# led-shift-r1.net
KiCad netlist of a schematic drawn in EAGLE
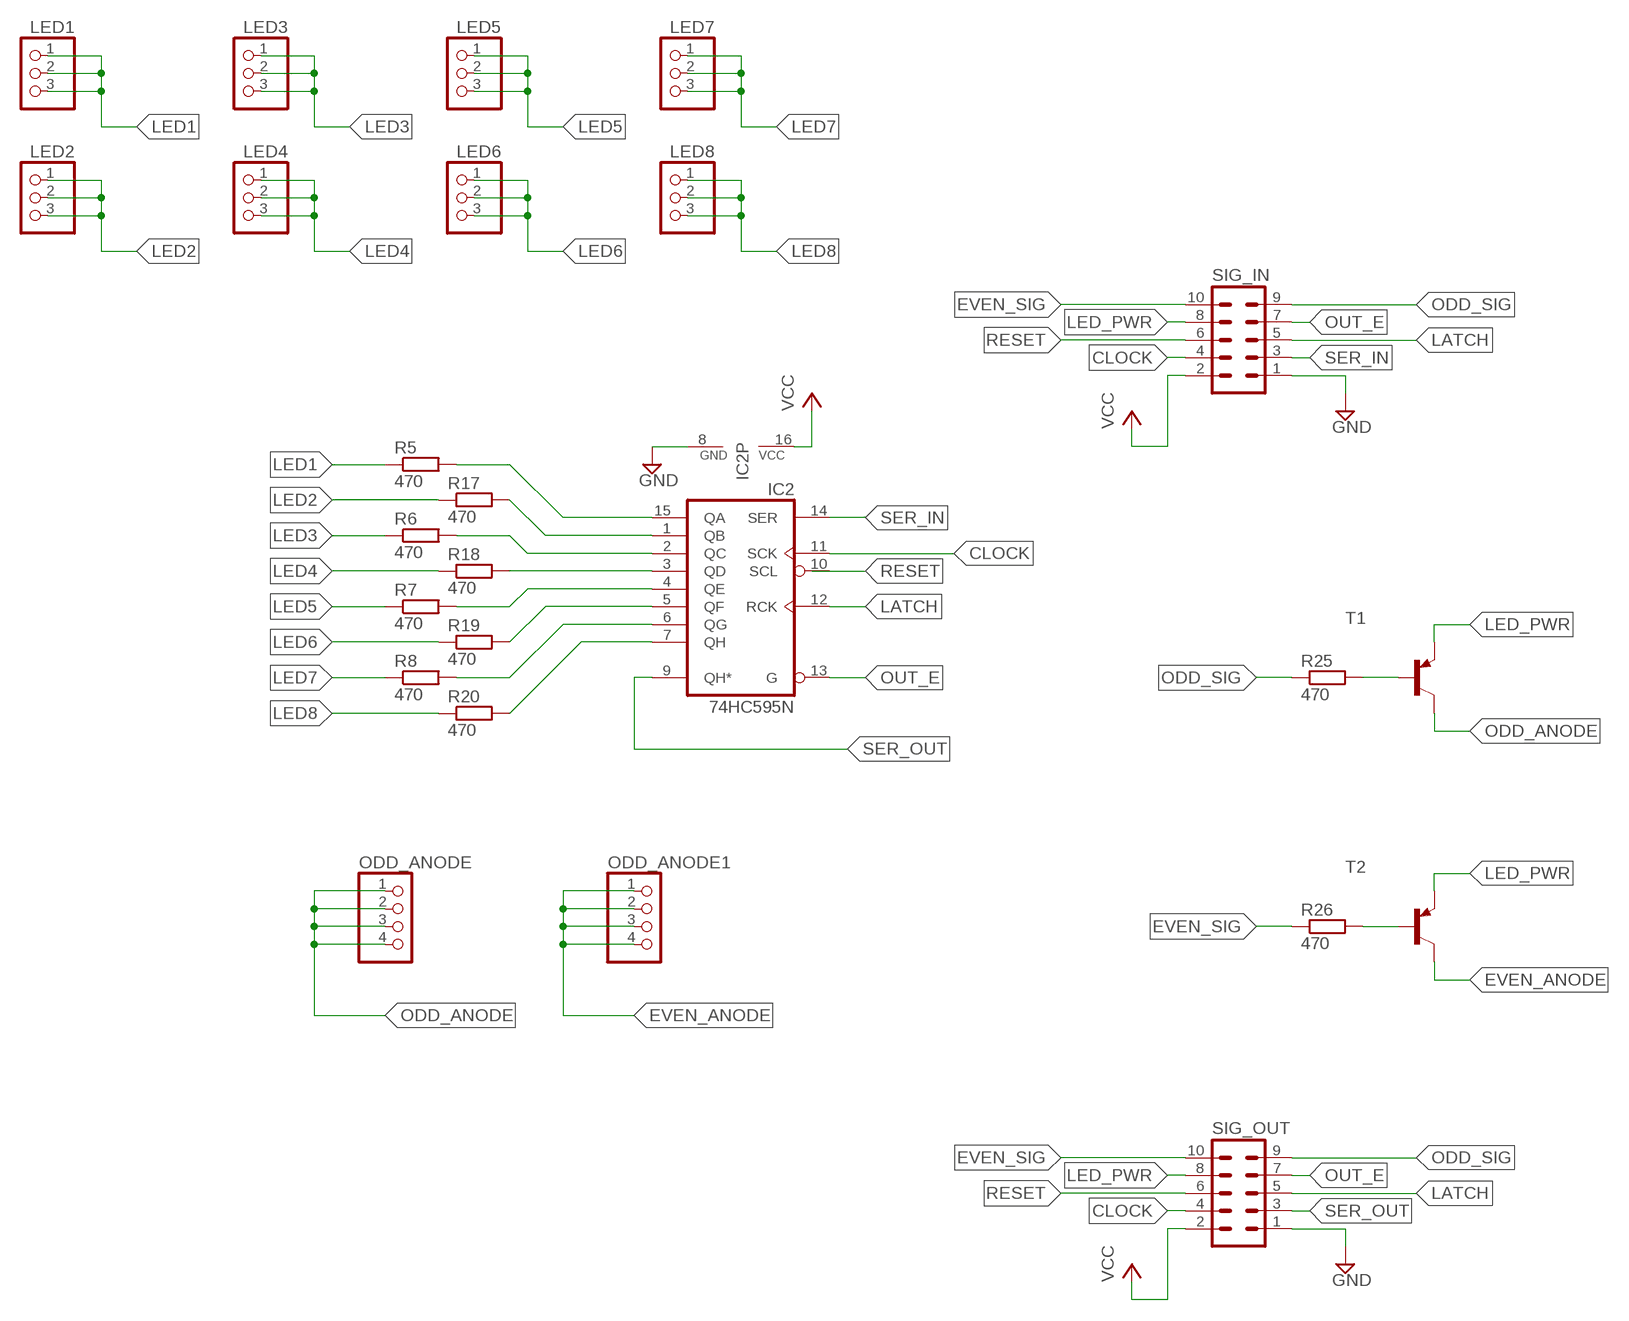
[diagram p0: schematic, sheet 1]

(export (version "E")
  (design (tool "Eeschema 10.0.6"))
  (components
    (comp (ref "IC2")
      (value "74HC595N")
      (footprint "eagle-import:DIL16")
      (libsource (lib "eagle-import") (part "74595NHC"))
    )
    (comp (ref "LED1")
      (value "PINHD-1X3")
      (footprint "eagle-import:1X03")
      (libsource (lib "eagle-import") (part "PINHD-1X3"))
    )
    (comp (ref "LED2")
      (value "PINHD-1X3")
      (footprint "eagle-import:1X03")
      (libsource (lib "eagle-import") (part "PINHD-1X3"))
    )
    (comp (ref "LED3")
      (value "PINHD-1X3")
      (footprint "eagle-import:1X03")
      (libsource (lib "eagle-import") (part "PINHD-1X3"))
    )
    (comp (ref "LED4")
      (value "PINHD-1X3")
      (footprint "eagle-import:1X03")
      (libsource (lib "eagle-import") (part "PINHD-1X3"))
    )
    (comp (ref "LED5")
      (value "PINHD-1X3")
      (footprint "eagle-import:1X03")
      (libsource (lib "eagle-import") (part "PINHD-1X3"))
    )
    (comp (ref "LED6")
      (value "PINHD-1X3")
      (footprint "eagle-import:1X03")
      (libsource (lib "eagle-import") (part "PINHD-1X3"))
    )
    (comp (ref "LED7")
      (value "PINHD-1X3")
      (footprint "eagle-import:1X03")
      (libsource (lib "eagle-import") (part "PINHD-1X3"))
    )
    (comp (ref "LED8")
      (value "PINHD-1X3")
      (footprint "eagle-import:1X03")
      (libsource (lib "eagle-import") (part "PINHD-1X3"))
    )
    (comp (ref "ODD_ANODE")
      (value "PINHD-1X4")
      (footprint "eagle-import:1X04")
      (libsource (lib "eagle-import") (part "PINHD-1X4"))
    )
    (comp (ref "ODD_ANODE1")
      (value "PINHD-1X4")
      (footprint "eagle-import:1X04")
      (libsource (lib "eagle-import") (part "PINHD-1X4"))
    )
    (comp (ref "R5")
      (value "470")
      (footprint "eagle-import:R0805")
      (libsource (lib "eagle-import") (part "R-EU_R0805"))
    )
    (comp (ref "R6")
      (value "470")
      (footprint "eagle-import:R0805")
      (libsource (lib "eagle-import") (part "R-EU_R0805"))
    )
    (comp (ref "R7")
      (value "470")
      (footprint "eagle-import:R0805")
      (libsource (lib "eagle-import") (part "R-EU_R0805"))
    )
    (comp (ref "R8")
      (value "470")
      (footprint "eagle-import:R0805")
      (libsource (lib "eagle-import") (part "R-EU_R0805"))
    )
    (comp (ref "R17")
      (value "470")
      (footprint "eagle-import:R0805")
      (libsource (lib "eagle-import") (part "R-EU_R0805"))
    )
    (comp (ref "R18")
      (value "470")
      (footprint "eagle-import:R0805")
      (libsource (lib "eagle-import") (part "R-EU_R0805"))
    )
    (comp (ref "R19")
      (value "470")
      (footprint "eagle-import:R0805")
      (libsource (lib "eagle-import") (part "R-EU_R0805"))
    )
    (comp (ref "R20")
      (value "470")
      (footprint "eagle-import:R0805")
      (libsource (lib "eagle-import") (part "R-EU_R0805"))
    )
    (comp (ref "R25")
      (value "470")
      (footprint "eagle-import:R0805")
      (libsource (lib "eagle-import") (part "R-EU_R0805"))
    )
    (comp (ref "R26")
      (value "470")
      (footprint "eagle-import:R0805")
      (libsource (lib "eagle-import") (part "R-EU_R0805"))
    )
    (comp (ref "SIG_IN")
      (value "MA05-2")
      (footprint "eagle-import:MA05-2")
      (libsource (lib "eagle-import") (part "MA05-2"))
    )
    (comp (ref "SIG_OUT")
      (value "MA05-2")
      (footprint "eagle-import:MA05-2")
      (libsource (lib "eagle-import") (part "MA05-2"))
    )
    (comp (ref "T1")
      (value "BC557B-PNP-TO92-EBC")
      (footprint "eagle-import:TO92-EBC")
      (libsource (lib "eagle-import") (part "-PNP-TO92-EBCBC557B"))
    )
    (comp (ref "T2")
      (value "BC557B-PNP-TO92-EBC")
      (footprint "eagle-import:TO92-EBC")
      (libsource (lib "eagle-import") (part "-PNP-TO92-EBCBC557B"))
    )
  )
  (nets
    (net (code "1") (name "CLOCK") (class "Default")
      (node (ref "IC2") (pin "11") (pinfunction "SCK_11") (pintype "input"))
      (node (ref "SIG_IN") (pin "4") (pinfunction "4_4") (pintype "passive"))
      (node (ref "SIG_OUT") (pin "4") (pinfunction "4_4") (pintype "passive"))
    )
    (net (code "2") (name "EVEN_ANODE") (class "Default")
      (node (ref "ODD_ANODE1") (pin "1") (pinfunction "1_1") (pintype "passive"))
      (node (ref "ODD_ANODE1") (pin "2") (pinfunction "2_2") (pintype "passive"))
      (node (ref "ODD_ANODE1") (pin "3") (pinfunction "3_3") (pintype "passive"))
      (node (ref "ODD_ANODE1") (pin "4") (pinfunction "4_4") (pintype "passive"))
      (node (ref "T2") (pin "C") (pinfunction "C_C") (pintype "passive"))
    )
    (net (code "3") (name "EVEN_SIG") (class "Default")
      (node (ref "R26") (pin "1") (pinfunction "1_1") (pintype "passive"))
      (node (ref "SIG_IN") (pin "10") (pinfunction "10_10") (pintype "passive"))
      (node (ref "SIG_OUT") (pin "10") (pinfunction "10_10") (pintype "passive"))
    )
    (net (code "4") (name "GND") (class "Default")
      (node (ref "IC2") (pin "8") (pinfunction "GND_8") (pintype "power_in"))
      (node (ref "SIG_IN") (pin "1") (pinfunction "1_1") (pintype "passive"))
      (node (ref "SIG_OUT") (pin "1") (pinfunction "1_1") (pintype "passive"))
    )
    (net (code "5") (name "LATCH") (class "Default")
      (node (ref "IC2") (pin "12") (pinfunction "RCK_12") (pintype "input"))
      (node (ref "SIG_IN") (pin "5") (pinfunction "5_5") (pintype "passive"))
      (node (ref "SIG_OUT") (pin "5") (pinfunction "5_5") (pintype "passive"))
    )
    (net (code "6") (name "LED1") (class "Default")
      (node (ref "LED1") (pin "1") (pinfunction "1_1") (pintype "passive"))
      (node (ref "LED1") (pin "2") (pinfunction "2_2") (pintype "passive"))
      (node (ref "LED1") (pin "3") (pinfunction "3_3") (pintype "passive"))
      (node (ref "R5") (pin "1") (pinfunction "1_1") (pintype "passive"))
    )
    (net (code "7") (name "LED2") (class "Default")
      (node (ref "LED2") (pin "1") (pinfunction "1_1") (pintype "passive"))
      (node (ref "LED2") (pin "2") (pinfunction "2_2") (pintype "passive"))
      (node (ref "LED2") (pin "3") (pinfunction "3_3") (pintype "passive"))
      (node (ref "R17") (pin "1") (pinfunction "1_1") (pintype "passive"))
    )
    (net (code "8") (name "LED3") (class "Default")
      (node (ref "LED3") (pin "1") (pinfunction "1_1") (pintype "passive"))
      (node (ref "LED3") (pin "2") (pinfunction "2_2") (pintype "passive"))
      (node (ref "LED3") (pin "3") (pinfunction "3_3") (pintype "passive"))
      (node (ref "R6") (pin "1") (pinfunction "1_1") (pintype "passive"))
    )
    (net (code "9") (name "LED4") (class "Default")
      (node (ref "LED4") (pin "1") (pinfunction "1_1") (pintype "passive"))
      (node (ref "LED4") (pin "2") (pinfunction "2_2") (pintype "passive"))
      (node (ref "LED4") (pin "3") (pinfunction "3_3") (pintype "passive"))
      (node (ref "R18") (pin "1") (pinfunction "1_1") (pintype "passive"))
    )
    (net (code "10") (name "LED5") (class "Default")
      (node (ref "LED5") (pin "1") (pinfunction "1_1") (pintype "passive"))
      (node (ref "LED5") (pin "2") (pinfunction "2_2") (pintype "passive"))
      (node (ref "LED5") (pin "3") (pinfunction "3_3") (pintype "passive"))
      (node (ref "R7") (pin "1") (pinfunction "1_1") (pintype "passive"))
    )
    (net (code "11") (name "LED6") (class "Default")
      (node (ref "LED6") (pin "1") (pinfunction "1_1") (pintype "passive"))
      (node (ref "LED6") (pin "2") (pinfunction "2_2") (pintype "passive"))
      (node (ref "LED6") (pin "3") (pinfunction "3_3") (pintype "passive"))
      (node (ref "R19") (pin "1") (pinfunction "1_1") (pintype "passive"))
    )
    (net (code "12") (name "LED7") (class "Default")
      (node (ref "LED7") (pin "1") (pinfunction "1_1") (pintype "passive"))
      (node (ref "LED7") (pin "2") (pinfunction "2_2") (pintype "passive"))
      (node (ref "LED7") (pin "3") (pinfunction "3_3") (pintype "passive"))
      (node (ref "R8") (pin "1") (pinfunction "1_1") (pintype "passive"))
    )
    (net (code "13") (name "LED8") (class "Default")
      (node (ref "LED8") (pin "1") (pinfunction "1_1") (pintype "passive"))
      (node (ref "LED8") (pin "2") (pinfunction "2_2") (pintype "passive"))
      (node (ref "LED8") (pin "3") (pinfunction "3_3") (pintype "passive"))
      (node (ref "R20") (pin "1") (pinfunction "1_1") (pintype "passive"))
    )
    (net (code "14") (name "LED_PWR") (class "Default")
      (node (ref "SIG_IN") (pin "8") (pinfunction "8_8") (pintype "passive"))
      (node (ref "SIG_OUT") (pin "8") (pinfunction "8_8") (pintype "passive"))
      (node (ref "T1") (pin "E") (pinfunction "E_E") (pintype "passive"))
      (node (ref "T2") (pin "E") (pinfunction "E_E") (pintype "passive"))
    )
    (net (code "15") (name "Net-(IC2A-QA)") (class "Default")
      (node (ref "IC2") (pin "15") (pinfunction "QA_15") (pintype "tri_state"))
      (node (ref "R5") (pin "2") (pinfunction "2_2") (pintype "passive"))
    )
    (net (code "16") (name "Net-(IC2A-QB)") (class "Default")
      (node (ref "IC2") (pin "1") (pinfunction "QB_1") (pintype "tri_state"))
      (node (ref "R17") (pin "2") (pinfunction "2_2") (pintype "passive"))
    )
    (net (code "17") (name "Net-(IC2A-QC)") (class "Default")
      (node (ref "IC2") (pin "2") (pinfunction "QC_2") (pintype "tri_state"))
      (node (ref "R6") (pin "2") (pinfunction "2_2") (pintype "passive"))
    )
    (net (code "18") (name "Net-(IC2A-QD)") (class "Default")
      (node (ref "IC2") (pin "3") (pinfunction "QD_3") (pintype "tri_state"))
      (node (ref "R18") (pin "2") (pinfunction "2_2") (pintype "passive"))
    )
    (net (code "19") (name "Net-(IC2A-QE)") (class "Default")
      (node (ref "IC2") (pin "4") (pinfunction "QE_4") (pintype "tri_state"))
      (node (ref "R7") (pin "2") (pinfunction "2_2") (pintype "passive"))
    )
    (net (code "20") (name "Net-(IC2A-QF)") (class "Default")
      (node (ref "IC2") (pin "5") (pinfunction "QF_5") (pintype "tri_state"))
      (node (ref "R19") (pin "2") (pinfunction "2_2") (pintype "passive"))
    )
    (net (code "21") (name "Net-(IC2A-QG)") (class "Default")
      (node (ref "IC2") (pin "6") (pinfunction "QG_6") (pintype "tri_state"))
      (node (ref "R8") (pin "2") (pinfunction "2_2") (pintype "passive"))
    )
    (net (code "22") (name "Net-(IC2A-QH)") (class "Default")
      (node (ref "IC2") (pin "7") (pinfunction "QH_7") (pintype "tri_state"))
      (node (ref "R20") (pin "2") (pinfunction "2_2") (pintype "passive"))
    )
    (net (code "23") (name "Net-(R25-Pad2)") (class "Default")
      (node (ref "R25") (pin "2") (pinfunction "2_2") (pintype "passive"))
      (node (ref "T1") (pin "B") (pinfunction "B_B") (pintype "passive"))
    )
    (net (code "24") (name "Net-(R26-Pad2)") (class "Default")
      (node (ref "R26") (pin "2") (pinfunction "2_2") (pintype "passive"))
      (node (ref "T2") (pin "B") (pinfunction "B_B") (pintype "passive"))
    )
    (net (code "25") (name "ODD_ANODE") (class "Default")
      (node (ref "ODD_ANODE") (pin "1") (pinfunction "1_1") (pintype "passive"))
      (node (ref "ODD_ANODE") (pin "2") (pinfunction "2_2") (pintype "passive"))
      (node (ref "ODD_ANODE") (pin "3") (pinfunction "3_3") (pintype "passive"))
      (node (ref "ODD_ANODE") (pin "4") (pinfunction "4_4") (pintype "passive"))
      (node (ref "T1") (pin "C") (pinfunction "C_C") (pintype "passive"))
    )
    (net (code "26") (name "ODD_SIG") (class "Default")
      (node (ref "R25") (pin "1") (pinfunction "1_1") (pintype "passive"))
      (node (ref "SIG_IN") (pin "9") (pinfunction "9_9") (pintype "passive"))
      (node (ref "SIG_OUT") (pin "9") (pinfunction "9_9") (pintype "passive"))
    )
    (net (code "27") (name "OUT_E") (class "Default")
      (node (ref "IC2") (pin "13") (pinfunction "G_13") (pintype "input"))
      (node (ref "SIG_IN") (pin "7") (pinfunction "7_7") (pintype "passive"))
      (node (ref "SIG_OUT") (pin "7") (pinfunction "7_7") (pintype "passive"))
    )
    (net (code "28") (name "RESET") (class "Default")
      (node (ref "SIG_IN") (pin "6") (pinfunction "6_6") (pintype "passive"))
      (node (ref "SIG_OUT") (pin "6") (pinfunction "6_6") (pintype "passive"))
    )
    (net (code "29") (name "SER_IN") (class "Default")
      (node (ref "IC2") (pin "14") (pinfunction "SER_14") (pintype "input"))
      (node (ref "SIG_IN") (pin "3") (pinfunction "3_3") (pintype "passive"))
    )
    (net (code "30") (name "SER_OUT") (class "Default")
      (node (ref "IC2") (pin "9") (pinfunction "QH*_9") (pintype "tri_state"))
      (node (ref "SIG_OUT") (pin "3") (pinfunction "3_3") (pintype "passive"))
    )
    (net (code "31") (name "VCC") (class "Default")
      (node (ref "IC2") (pin "16") (pinfunction "VCC_16") (pintype "power_in"))
      (node (ref "SIG_IN") (pin "2") (pinfunction "2_2") (pintype "passive"))
      (node (ref "SIG_OUT") (pin "2") (pinfunction "2_2") (pintype "passive"))
    )
    (net (code "32") (name "unconnected-(IC2A-SCL-Pad10)") (class "Default")
      (node (ref "IC2") (pin "10") (pinfunction "SCL_10") (pintype "input"))
    )
  )
)
